# brick_analog_mic.net
KiCad netlist of a schematic drawn in EAGLE
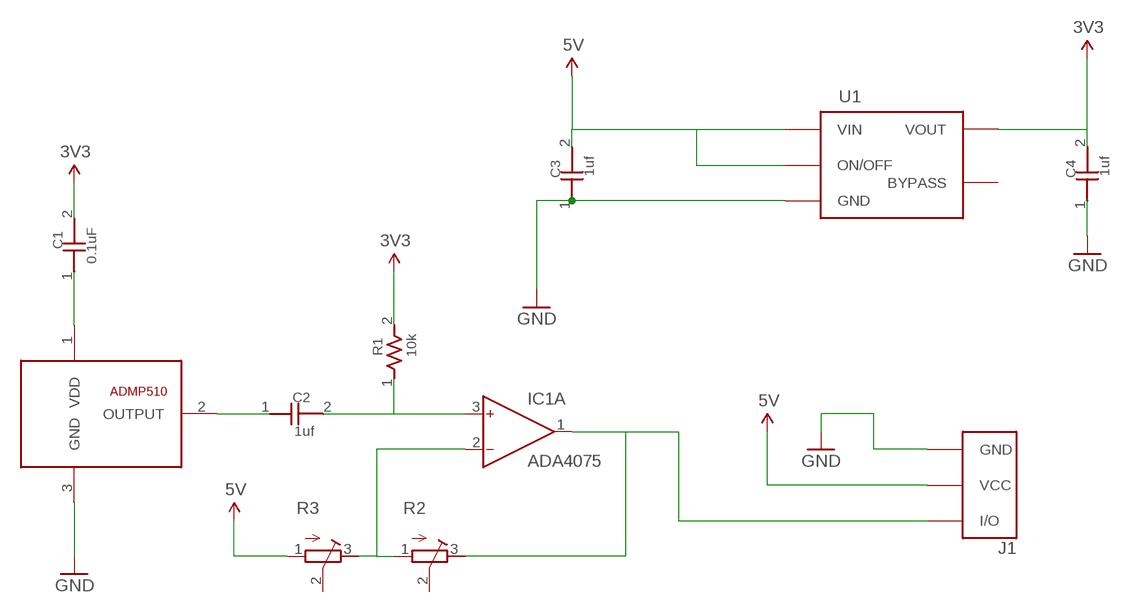
[diagram p0: schematic, sheet 1]

(export (version "E")
  (design (tool "Eeschema 10.0.6"))
  (components
    (comp (ref "C1")
      (value "0.1uF")
      (footprint "eagle-import:0603")
      (libsource (lib "eagle-import") (part "CAPACITOR0603"))
    )
    (comp (ref "C2")
      (value "1uf")
      (footprint "eagle-import:0603")
      (libsource (lib "eagle-import") (part "CAPACITOR0603"))
    )
    (comp (ref "C3")
      (value "1uf")
      (footprint "eagle-import:0603")
      (libsource (lib "eagle-import") (part "GClue-Capacitor_CAPACITOR0603"))
    )
    (comp (ref "C4")
      (value "1uf")
      (footprint "eagle-import:0603")
      (libsource (lib "eagle-import") (part "GClue-Capacitor_CAPACITOR0603"))
    )
    (comp (ref "IC1")
      (value "ADA4075")
      (footprint "eagle-import:SO8")
      (fields (field (name "MPN") "ADA4075-2ARZ"))
      (libsource (lib "eagle-import") (part "ADA4075-2R"))
    )
    (comp (ref "J1")
      (value "FABO_BRICK_3PIN")
      (footprint "eagle-import:FABO_BRICK_3PIN")
      (libsource (lib "eagle-import") (part "FABO_BRICK_3PIN"))
    )
    (comp (ref "R1")
      (value "10k")
      (footprint "eagle-import:0603")
      (libsource (lib "eagle-import") (part "RESISTOR0603"))
    )
    (comp (ref "R2")
      (value "R-TRIMM3202")
      (footprint "eagle-import:RTRIM3202")
      (libsource (lib "eagle-import") (part "R-TRIMM3202"))
    )
    (comp (ref "R3")
      (value "R-TRIMM3202")
      (footprint "eagle-import:RTRIM3202")
      (libsource (lib "eagle-import") (part "R-TRIMM3202"))
    )
    (comp (ref "U$1")
      (value "ANALOGDEVICES-ADMP510")
      (footprint "eagle-import:ANALOGDEVICES-ADMP510")
      (libsource (lib "eagle-import") (part "ANALOGDEVICES-ADMP510"))
    )
    (comp (ref "U1")
      (value "LP2985-33DBVR")
      (footprint "eagle-import:SOT_23_5")
      (libsource (lib "eagle-import") (part "LP2985-33DBVR"))
    )
  )
  (nets
    (net (code "1") (name "3V3") (class "Default")
      (node (ref "C1") (pin "2") (pinfunction "2_2") (pintype "passive"))
      (node (ref "C4") (pin "2") (pinfunction "2_2") (pintype "passive"))
      (node (ref "R1") (pin "2") (pinfunction "2_2") (pintype "passive"))
      (node (ref "U1") (pin "5") (pinfunction "VOUT_5") (pintype "output"))
    )
    (net (code "2") (name "5V") (class "Default")
      (node (ref "C3") (pin "2") (pinfunction "2_2") (pintype "passive"))
      (node (ref "J1") (pin "VCC") (pinfunction "VCC_VCC") (pintype "bidirectional"))
      (node (ref "R3") (pin "1") (pinfunction "A_1") (pintype "passive"))
      (node (ref "U1") (pin "1") (pinfunction "VIN_1") (pintype "input"))
      (node (ref "U1") (pin "3") (pinfunction "ON/OFF_3") (pintype "input"))
    )
    (net (code "3") (name "GND") (class "Default")
      (node (ref "C3") (pin "1") (pinfunction "1_1") (pintype "passive"))
      (node (ref "C4") (pin "1") (pinfunction "1_1") (pintype "passive"))
      (node (ref "J1") (pin "GND") (pinfunction "GND_GND") (pintype "bidirectional"))
      (node (ref "U$1") (pin "3") (pinfunction "GND_3") (pintype "bidirectional"))
      (node (ref "U1") (pin "2") (pinfunction "GND_2") (pintype "power_in"))
    )
    (net (code "4") (name "Net-(IC1A-IN+)") (class "Default")
      (node (ref "C2") (pin "2") (pinfunction "2_2") (pintype "passive"))
      (node (ref "IC1") (pin "3") (pinfunction "IN+_3") (pintype "input"))
      (node (ref "R1") (pin "1") (pinfunction "1_1") (pintype "passive"))
    )
    (net (code "5") (name "Net-(IC1A-IN-)") (class "Default")
      (node (ref "IC1") (pin "2") (pinfunction "IN-_2") (pintype "input"))
      (node (ref "R2") (pin "1") (pinfunction "A_1") (pintype "passive"))
      (node (ref "R3") (pin "3") (pinfunction "E_3") (pintype "passive"))
    )
    (net (code "6") (name "Net-(IC1A-OUT)") (class "Default")
      (node (ref "IC1") (pin "1") (pinfunction "OUT_1") (pintype "output"))
      (node (ref "J1") (pin "IN/OUT") (pinfunction "I/O_IN/OUT") (pintype "bidirectional"))
      (node (ref "R2") (pin "3") (pinfunction "E_3") (pintype "passive"))
    )
    (net (code "7") (name "Net-(U$1-OUTPUT)") (class "Default")
      (node (ref "C2") (pin "1") (pinfunction "1_1") (pintype "passive"))
      (node (ref "U$1") (pin "2") (pinfunction "OUTPUT_2") (pintype "bidirectional"))
    )
    (net (code "8") (name "Net-(U$1-VDD)") (class "Default")
      (node (ref "C1") (pin "1") (pinfunction "1_1") (pintype "passive"))
      (node (ref "U$1") (pin "1") (pinfunction "VDD_1") (pintype "bidirectional"))
    )
    (net (code "9") (name "unconnected-(R2-S-Pad2)") (class "Default")
      (node (ref "R2") (pin "2") (pinfunction "S_2") (pintype "passive"))
    )
    (net (code "10") (name "unconnected-(R3-S-Pad2)") (class "Default")
      (node (ref "R3") (pin "2") (pinfunction "S_2") (pintype "passive"))
    )
    (net (code "11") (name "unconnected-(U1-BYPASS-Pad4)") (class "Default")
      (node (ref "U1") (pin "4") (pinfunction "BYPASS_4") (pintype "bidirectional"))
    )
  )
)
